# UI.net
KiCad netlist of a schematic drawn in Altium Designer
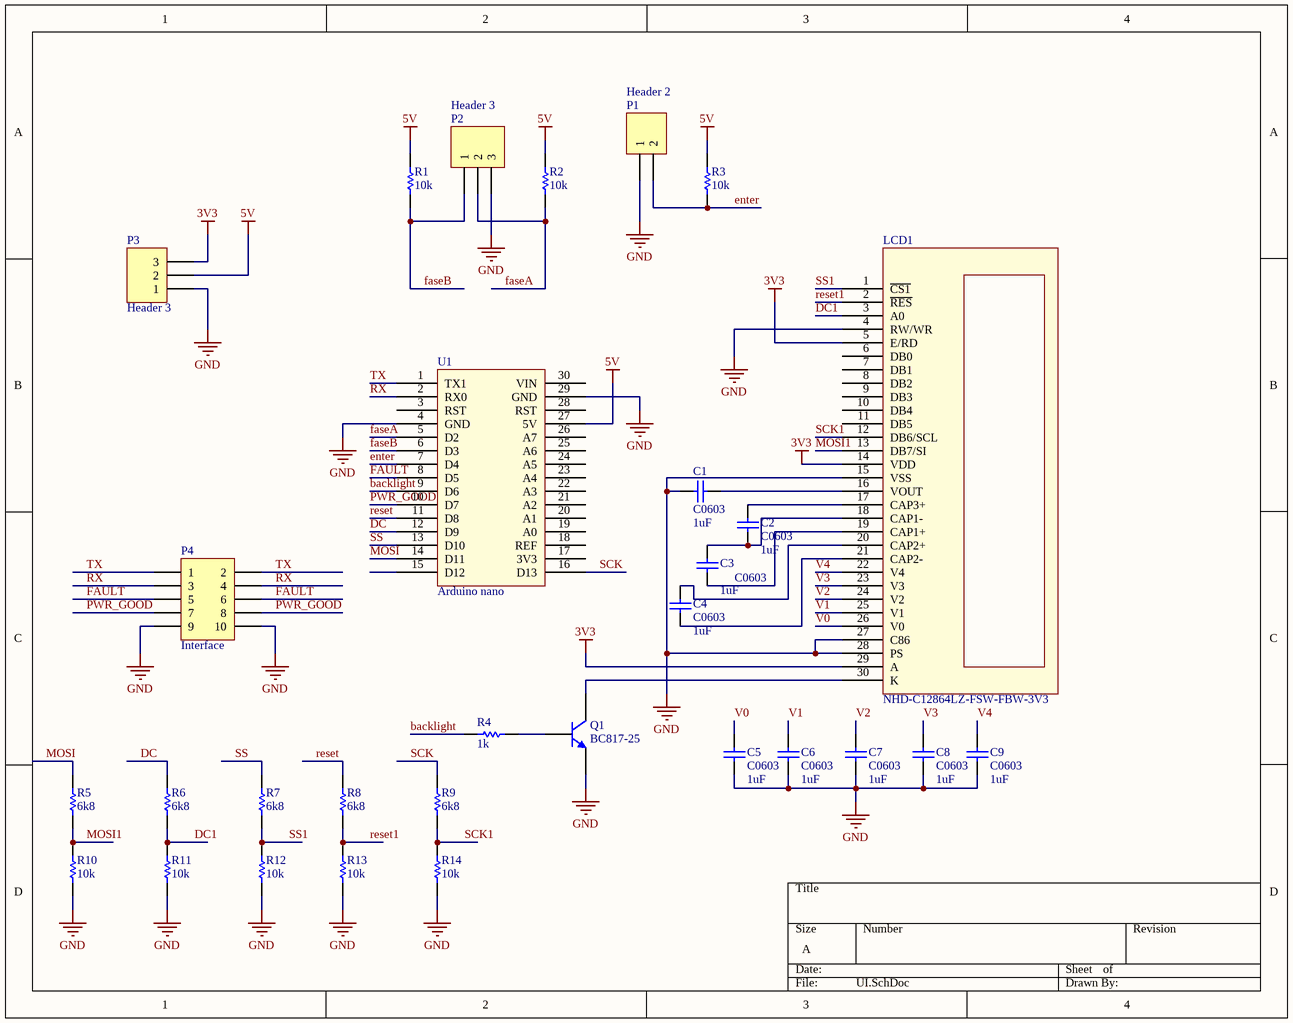
[diagram p0: UI.SchDoc]

(export (version "E")
  (design (tool "Eeschema 10.0.6"))
  (components
    (comp (ref "C1")
      (value "C0603")
      (footprint "0603")
      (description "C1608X7R1C105K X7R")
      (fields (field (name "ALTIUM_VALUE") "1uF") (field (name "PUBLISHER") "Altium Limited"))
      (libsource (lib "KEMET Chip Capacitor") (part "C0603"))
    )
    (comp (ref "C2")
      (value "C0603")
      (footprint "0603")
      (description "C1608X7R1C105K X7R")
      (fields (field (name "ALTIUM_VALUE") "1uF") (field (name "PUBLISHER") "Altium Limited"))
      (libsource (lib "KEMET Chip Capacitor") (part "C0603"))
    )
    (comp (ref "C3")
      (value "C0603")
      (footprint "0603")
      (description "C1608X7R1C105K X7R")
      (fields (field (name "ALTIUM_VALUE") "1uF") (field (name "PUBLISHER") "Altium Limited"))
      (libsource (lib "KEMET Chip Capacitor") (part "C0603"))
    )
    (comp (ref "C4")
      (value "C0603")
      (footprint "0603")
      (description "C1608X7R1C105K X7R")
      (fields (field (name "ALTIUM_VALUE") "1uF") (field (name "PUBLISHER") "Altium Limited"))
      (libsource (lib "KEMET Chip Capacitor") (part "C0603"))
    )
    (comp (ref "C5")
      (value "C0603")
      (footprint "0603")
      (description "C1608X7R1C105K X7R")
      (fields (field (name "ALTIUM_VALUE") "1uF") (field (name "PUBLISHER") "Altium Limited"))
      (libsource (lib "KEMET Chip Capacitor") (part "C0603"))
    )
    (comp (ref "C6")
      (value "C0603")
      (footprint "0603")
      (description "C1608X7R1C105K X7R")
      (fields (field (name "ALTIUM_VALUE") "1uF") (field (name "PUBLISHER") "Altium Limited"))
      (libsource (lib "KEMET Chip Capacitor") (part "C0603"))
    )
    (comp (ref "C7")
      (value "C0603")
      (footprint "0603")
      (description "C1608X7R1C105K X7R")
      (fields (field (name "ALTIUM_VALUE") "1uF") (field (name "PUBLISHER") "Altium Limited"))
      (libsource (lib "KEMET Chip Capacitor") (part "C0603"))
    )
    (comp (ref "C8")
      (value "C0603")
      (footprint "0603")
      (description "C1608X7R1C105K X7R")
      (fields (field (name "ALTIUM_VALUE") "1uF") (field (name "PUBLISHER") "Altium Limited"))
      (libsource (lib "KEMET Chip Capacitor") (part "C0603"))
    )
    (comp (ref "C9")
      (value "C0603")
      (footprint "0603")
      (description "C1608X7R1C105K X7R")
      (fields (field (name "ALTIUM_VALUE") "1uF") (field (name "PUBLISHER") "Altium Limited"))
      (libsource (lib "KEMET Chip Capacitor") (part "C0603"))
    )
    (comp (ref "LCD1")
      (value "NHD-C12864LZ-FSW-FBW-3V3")
      (footprint "NHD-C12864LZ-FSW-FBW-3V3")
      (libsource (lib "NXT - IC") (part "NHD-C12864LZ-FSW-FBW-3V3"))
    )
    (comp (ref "P1")
      (value "Header 2")
      (footprint "HDR1X2")
      (description "Header, 2-Pin")
      (fields (field (name "PUBLISHER") "Altium Limited"))
      (libsource (lib "Miscellaneous Connectors") (part "Header 2"))
    )
    (comp (ref "P2")
      (value "Header 3")
      (footprint "HDR1X3")
      (description "Header, 3-Pin")
      (fields (field (name "PUBLISHER") "Altium Limited"))
      (libsource (lib "Miscellaneous Connectors") (part "Header 3"))
    )
    (comp (ref "P3")
      (value "Header 3")
      (footprint "HDR1X3")
      (description "Header, 3-Pin")
      (fields (field (name "PUBLISHER") "Altium Limited"))
      (libsource (lib "") (part "Header 3_1"))
    )
    (comp (ref "P4")
      (value "Interface")
      (footprint "HDR2X5")
      (description "Header, 5-Pin, Dual row")
      (fields (field (name "PUBLISHER") "Altium Limited"))
      (libsource (lib "Miscellaneous Connectors") (part "Header 5X2"))
    )
    (comp (ref "Q1")
      (value "BC817-25")
      (footprint "SOT-23A_N")
      (description "NPN General Purpose Amplifier")
      (fields (field (name "PUBLISHER") "Altium Limited"))
      (libsource (lib "FSC Discrete BJT") (part "BC817-25"))
    )
    (comp (ref "R1")
      (value "10k")
      (footprint "8RB-1206")
      (fields (field (name "Comment") "SMD") (field (name "PUBLISHER") "Altium Limited"))
      (libsource (lib "Panasonic Resistor") (part "ERJ8BQ"))
    )
    (comp (ref "R2")
      (value "10k")
      (footprint "8RB-1206")
      (fields (field (name "Comment") "SMD") (field (name "PUBLISHER") "Altium Limited"))
      (libsource (lib "Panasonic Resistor") (part "ERJ8BQ"))
    )
    (comp (ref "R3")
      (value "10k")
      (footprint "8RB-1206")
      (fields (field (name "Comment") "SMD") (field (name "PUBLISHER") "Altium Limited"))
      (libsource (lib "Panasonic Resistor") (part "ERJ8BQ"))
    )
    (comp (ref "R4")
      (value "1k")
      (footprint "8RB-1206")
      (fields (field (name "Comment") "SMD") (field (name "PUBLISHER") "Altium Limited"))
      (libsource (lib "Panasonic Resistor") (part "ERJ8BQ"))
    )
    (comp (ref "R5")
      (value "6k8")
      (footprint "8RB-1206")
      (fields (field (name "Comment") "SMD") (field (name "PUBLISHER") "Altium Limited"))
      (libsource (lib "Panasonic Resistor") (part "ERJ8BQ"))
    )
    (comp (ref "R6")
      (value "6k8")
      (footprint "8RB-1206")
      (fields (field (name "Comment") "SMD") (field (name "PUBLISHER") "Altium Limited"))
      (libsource (lib "Panasonic Resistor") (part "ERJ8BQ"))
    )
    (comp (ref "R7")
      (value "6k8")
      (footprint "8RB-1206")
      (fields (field (name "Comment") "SMD") (field (name "PUBLISHER") "Altium Limited"))
      (libsource (lib "Panasonic Resistor") (part "ERJ8BQ"))
    )
    (comp (ref "R8")
      (value "6k8")
      (footprint "8RB-1206")
      (fields (field (name "Comment") "SMD") (field (name "PUBLISHER") "Altium Limited"))
      (libsource (lib "Panasonic Resistor") (part "ERJ8BQ"))
    )
    (comp (ref "R9")
      (value "6k8")
      (footprint "8RB-1206")
      (fields (field (name "Comment") "SMD") (field (name "PUBLISHER") "Altium Limited"))
      (libsource (lib "Panasonic Resistor") (part "ERJ8BQ"))
    )
    (comp (ref "R10")
      (value "10k")
      (footprint "8RB-1206")
      (fields (field (name "Comment") "SMD") (field (name "PUBLISHER") "Altium Limited"))
      (libsource (lib "Panasonic Resistor") (part "ERJ8BQ"))
    )
    (comp (ref "R11")
      (value "10k")
      (footprint "8RB-1206")
      (fields (field (name "Comment") "SMD") (field (name "PUBLISHER") "Altium Limited"))
      (libsource (lib "Panasonic Resistor") (part "ERJ8BQ"))
    )
    (comp (ref "R12")
      (value "10k")
      (footprint "8RB-1206")
      (fields (field (name "Comment") "SMD") (field (name "PUBLISHER") "Altium Limited"))
      (libsource (lib "Panasonic Resistor") (part "ERJ8BQ"))
    )
    (comp (ref "R13")
      (value "10k")
      (footprint "8RB-1206")
      (fields (field (name "Comment") "SMD") (field (name "PUBLISHER") "Altium Limited"))
      (libsource (lib "Panasonic Resistor") (part "ERJ8BQ"))
    )
    (comp (ref "R14")
      (value "10k")
      (footprint "8RB-1206")
      (fields (field (name "Comment") "SMD") (field (name "PUBLISHER") "Altium Limited"))
      (libsource (lib "Panasonic Resistor") (part "ERJ8BQ"))
    )
    (comp (ref "U1")
      (value "Arduino nano")
      (footprint "ARDUINO NANO")
      (libsource (lib "NXT") (part "arduino nano"))
    )
  )
  (nets
    (net (code "1") (name "/DC") (class "Default")
      (node (ref "R6") (pin "2") (pinfunction "2_2") (pintype "passive"))
      (node (ref "U1") (pin "12") (pinfunction "D9_12") (pintype "passive"))
    )
    (net (code "2") (name "/DC1") (class "Default")
      (node (ref "LCD1") (pin "3") (pinfunction "A0_3") (pintype "passive"))
      (node (ref "R11") (pin "2") (pinfunction "2_2") (pintype "passive"))
      (node (ref "R6") (pin "1") (pinfunction "1_1") (pintype "passive"))
    )
    (net (code "3") (name "/FAULT") (class "Default")
      (node (ref "P4") (pin "5") (pinfunction "5_5") (pintype "passive"))
      (node (ref "P4") (pin "6") (pinfunction "6_6") (pintype "passive"))
      (node (ref "U1") (pin "8") (pinfunction "D5_8") (pintype "passive"))
    )
    (net (code "4") (name "/MOSI") (class "Default")
      (node (ref "R5") (pin "2") (pinfunction "2_2") (pintype "passive"))
      (node (ref "U1") (pin "14") (pinfunction "D11_14") (pintype "passive"))
    )
    (net (code "5") (name "/MOSI1") (class "Default")
      (node (ref "LCD1") (pin "13") (pinfunction "DB7/SI_13") (pintype "passive"))
      (node (ref "R10") (pin "2") (pinfunction "2_2") (pintype "passive"))
      (node (ref "R5") (pin "1") (pinfunction "1_1") (pintype "passive"))
    )
    (net (code "6") (name "/PWR_GOOD") (class "Default")
      (node (ref "P4") (pin "7") (pinfunction "7_7") (pintype "passive"))
      (node (ref "P4") (pin "8") (pinfunction "8_8") (pintype "passive"))
      (node (ref "U1") (pin "10") (pinfunction "D7_10") (pintype "passive"))
    )
    (net (code "7") (name "/RX") (class "Default")
      (node (ref "P4") (pin "3") (pinfunction "3_3") (pintype "passive"))
      (node (ref "P4") (pin "4") (pinfunction "4_4") (pintype "passive"))
      (node (ref "U1") (pin "2") (pinfunction "RX0_2") (pintype "passive"))
    )
    (net (code "8") (name "/SCK") (class "Default")
      (node (ref "R9") (pin "2") (pinfunction "2_2") (pintype "passive"))
      (node (ref "U1") (pin "16") (pinfunction "D13_16") (pintype "passive"))
    )
    (net (code "9") (name "/SCK1") (class "Default")
      (node (ref "LCD1") (pin "12") (pinfunction "DB6/SCL_12") (pintype "passive"))
      (node (ref "R14") (pin "2") (pinfunction "2_2") (pintype "passive"))
      (node (ref "R9") (pin "1") (pinfunction "1_1") (pintype "passive"))
    )
    (net (code "10") (name "/SS") (class "Default")
      (node (ref "R7") (pin "2") (pinfunction "2_2") (pintype "passive"))
      (node (ref "U1") (pin "13") (pinfunction "D10_13") (pintype "passive"))
    )
    (net (code "11") (name "/SS1") (class "Default")
      (node (ref "LCD1") (pin "1") (pinfunction "~{CS1}_1") (pintype "passive"))
      (node (ref "R12") (pin "2") (pinfunction "2_2") (pintype "passive"))
      (node (ref "R7") (pin "1") (pinfunction "1_1") (pintype "passive"))
    )
    (net (code "12") (name "/TX") (class "Default")
      (node (ref "P4") (pin "1") (pinfunction "1_1") (pintype "passive"))
      (node (ref "P4") (pin "2") (pinfunction "2_2") (pintype "passive"))
      (node (ref "U1") (pin "1") (pinfunction "TX1_1") (pintype "passive"))
    )
    (net (code "13") (name "/V0") (class "Default")
      (node (ref "C5") (pin "2") (pinfunction "2_2") (pintype "passive"))
      (node (ref "LCD1") (pin "26") (pinfunction "V0_26") (pintype "passive"))
    )
    (net (code "14") (name "/V1") (class "Default")
      (node (ref "C6") (pin "2") (pinfunction "2_2") (pintype "passive"))
      (node (ref "LCD1") (pin "25") (pinfunction "V1_25") (pintype "passive"))
    )
    (net (code "15") (name "/V2") (class "Default")
      (node (ref "C7") (pin "2") (pinfunction "2_2") (pintype "passive"))
      (node (ref "LCD1") (pin "24") (pinfunction "V2_24") (pintype "passive"))
    )
    (net (code "16") (name "/V3") (class "Default")
      (node (ref "C8") (pin "2") (pinfunction "2_2") (pintype "passive"))
      (node (ref "LCD1") (pin "23") (pinfunction "V3_23") (pintype "passive"))
    )
    (net (code "17") (name "/V4") (class "Default")
      (node (ref "C9") (pin "2") (pinfunction "2_2") (pintype "passive"))
      (node (ref "LCD1") (pin "22") (pinfunction "V4_22") (pintype "passive"))
    )
    (net (code "18") (name "/backlight") (class "Default")
      (node (ref "R4") (pin "2") (pinfunction "2_2") (pintype "passive"))
      (node (ref "U1") (pin "9") (pinfunction "D6_9") (pintype "passive"))
    )
    (net (code "19") (name "/enter") (class "Default")
      (node (ref "P1") (pin "2") (pinfunction "2_2") (pintype "passive"))
      (node (ref "R3") (pin "1") (pinfunction "1_1") (pintype "passive"))
      (node (ref "U1") (pin "7") (pinfunction "D4_7") (pintype "passive"))
    )
    (net (code "20") (name "/faseA") (class "Default")
      (node (ref "P2") (pin "2") (pinfunction "2_2") (pintype "passive"))
      (node (ref "R2") (pin "1") (pinfunction "1_1") (pintype "passive"))
      (node (ref "U1") (pin "5") (pinfunction "D2_5") (pintype "passive"))
    )
    (net (code "21") (name "/faseB") (class "Default")
      (node (ref "P2") (pin "1") (pinfunction "1_1") (pintype "passive"))
      (node (ref "R1") (pin "1") (pinfunction "1_1") (pintype "passive"))
      (node (ref "U1") (pin "6") (pinfunction "D3_6") (pintype "passive"))
    )
    (net (code "22") (name "/reset") (class "Default")
      (node (ref "R8") (pin "2") (pinfunction "2_2") (pintype "passive"))
      (node (ref "U1") (pin "11") (pinfunction "D8_11") (pintype "passive"))
    )
    (net (code "23") (name "/reset1") (class "Default")
      (node (ref "LCD1") (pin "2") (pinfunction "~{RES}_2") (pintype "passive"))
      (node (ref "R13") (pin "2") (pinfunction "2_2") (pintype "passive"))
      (node (ref "R8") (pin "1") (pinfunction "1_1") (pintype "passive"))
    )
    (net (code "24") (name "3V3") (class "Default")
      (node (ref "LCD1") (pin "14") (pinfunction "VDD_14") (pintype "passive"))
      (node (ref "LCD1") (pin "29") (pinfunction "A_29") (pintype "passive"))
      (node (ref "LCD1") (pin "5") (pinfunction "E/RD_5") (pintype "passive"))
      (node (ref "P3") (pin "3") (pinfunction "3_3") (pintype "passive"))
    )
    (net (code "25") (name "5V") (class "Default")
      (node (ref "P3") (pin "2") (pinfunction "2_2") (pintype "passive"))
      (node (ref "R1") (pin "2") (pinfunction "2_2") (pintype "passive"))
      (node (ref "R2") (pin "2") (pinfunction "2_2") (pintype "passive"))
      (node (ref "R3") (pin "2") (pinfunction "2_2") (pintype "passive"))
      (node (ref "U1") (pin "27") (pinfunction "5V_27") (pintype "passive"))
    )
    (net (code "26") (name "GND") (class "Default")
      (node (ref "C1") (pin "2") (pinfunction "2_2") (pintype "passive"))
      (node (ref "C5") (pin "1") (pinfunction "1_1") (pintype "passive"))
      (node (ref "C6") (pin "1") (pinfunction "1_1") (pintype "passive"))
      (node (ref "C7") (pin "1") (pinfunction "1_1") (pintype "passive"))
      (node (ref "C8") (pin "1") (pinfunction "1_1") (pintype "passive"))
      (node (ref "C9") (pin "1") (pinfunction "1_1") (pintype "passive"))
      (node (ref "LCD1") (pin "15") (pinfunction "VSS_15") (pintype "passive"))
      (node (ref "LCD1") (pin "27") (pinfunction "C86_27") (pintype "passive"))
      (node (ref "LCD1") (pin "28") (pinfunction "PS_28") (pintype "passive"))
      (node (ref "LCD1") (pin "4") (pinfunction "RW/WR_4") (pintype "passive"))
      (node (ref "P1") (pin "1") (pinfunction "1_1") (pintype "passive"))
      (node (ref "P2") (pin "3") (pinfunction "3_3") (pintype "passive"))
      (node (ref "P3") (pin "1") (pinfunction "1_1") (pintype "passive"))
      (node (ref "P4") (pin "10") (pinfunction "10_10") (pintype "passive"))
      (node (ref "P4") (pin "9") (pinfunction "9_9") (pintype "passive"))
      (node (ref "Q1") (pin "2") (pinfunction "E_2") (pintype "passive"))
      (node (ref "R10") (pin "1") (pinfunction "1_1") (pintype "passive"))
      (node (ref "R11") (pin "1") (pinfunction "1_1") (pintype "passive"))
      (node (ref "R12") (pin "1") (pinfunction "1_1") (pintype "passive"))
      (node (ref "R13") (pin "1") (pinfunction "1_1") (pintype "passive"))
      (node (ref "R14") (pin "1") (pinfunction "1_1") (pintype "passive"))
      (node (ref "U1") (pin "29") (pinfunction "GND_29") (pintype "passive"))
      (node (ref "U1") (pin "4") (pinfunction "GND_4") (pintype "passive"))
    )
    (net (code "27") (name "Net-(LCD1-CAP1+)") (class "Default")
      (node (ref "C3") (pin "1") (pinfunction "1_1") (pintype "passive"))
      (node (ref "LCD1") (pin "19") (pinfunction "CAP1+_19") (pintype "passive"))
    )
    (net (code "28") (name "Net-(LCD1-CAP1-)") (class "Default")
      (node (ref "C2") (pin "1") (pinfunction "1_1") (pintype "passive"))
      (node (ref "C3") (pin "2") (pinfunction "2_2") (pintype "passive"))
      (node (ref "LCD1") (pin "18") (pinfunction "CAP1-_18") (pintype "passive"))
    )
    (net (code "29") (name "Net-(LCD1-CAP2+)") (class "Default")
      (node (ref "C4") (pin "2") (pinfunction "2_2") (pintype "passive"))
      (node (ref "LCD1") (pin "20") (pinfunction "CAP2+_20") (pintype "passive"))
    )
    (net (code "30") (name "Net-(LCD1-CAP2-)") (class "Default")
      (node (ref "C4") (pin "1") (pinfunction "1_1") (pintype "passive"))
      (node (ref "LCD1") (pin "21") (pinfunction "CAP2-_21") (pintype "passive"))
    )
    (net (code "31") (name "Net-(LCD1-CAP3+)") (class "Default")
      (node (ref "C2") (pin "2") (pinfunction "2_2") (pintype "passive"))
      (node (ref "LCD1") (pin "17") (pinfunction "CAP3+_17") (pintype "passive"))
    )
    (net (code "32") (name "Net-(LCD1-K)") (class "Default")
      (node (ref "LCD1") (pin "30") (pinfunction "K_30") (pintype "passive"))
      (node (ref "Q1") (pin "3") (pinfunction "C_3") (pintype "passive"))
    )
    (net (code "33") (name "Net-(LCD1-VOUT)") (class "Default")
      (node (ref "C1") (pin "1") (pinfunction "1_1") (pintype "passive"))
      (node (ref "LCD1") (pin "16") (pinfunction "VOUT_16") (pintype "passive"))
    )
    (net (code "34") (name "Net-(Q1-B)") (class "Default")
      (node (ref "Q1") (pin "1") (pinfunction "B_1") (pintype "passive"))
      (node (ref "R4") (pin "1") (pinfunction "1_1") (pintype "passive"))
    )
    (net (code "35") (name "unconnected-(LCD1-DB0-Pad6)") (class "Default")
      (node (ref "LCD1") (pin "6") (pinfunction "DB0_6") (pintype "passive"))
    )
    (net (code "36") (name "unconnected-(LCD1-DB1-Pad7)") (class "Default")
      (node (ref "LCD1") (pin "7") (pinfunction "DB1_7") (pintype "passive"))
    )
    (net (code "37") (name "unconnected-(LCD1-DB2-Pad8)") (class "Default")
      (node (ref "LCD1") (pin "8") (pinfunction "DB2_8") (pintype "passive"))
    )
    (net (code "38") (name "unconnected-(LCD1-DB3-Pad9)") (class "Default")
      (node (ref "LCD1") (pin "9") (pinfunction "DB3_9") (pintype "passive"))
    )
    (net (code "39") (name "unconnected-(LCD1-DB4-Pad10)") (class "Default")
      (node (ref "LCD1") (pin "10") (pinfunction "DB4_10") (pintype "passive"))
    )
    (net (code "40") (name "unconnected-(LCD1-DB5-Pad11)") (class "Default")
      (node (ref "LCD1") (pin "11") (pinfunction "DB5_11") (pintype "passive"))
    )
    (net (code "41") (name "unconnected-(U1-3V3-Pad17)") (class "Default")
      (node (ref "U1") (pin "17") (pinfunction "3V3_17") (pintype "passive"))
    )
    (net (code "42") (name "unconnected-(U1-A0-Pad19)") (class "Default")
      (node (ref "U1") (pin "19") (pinfunction "A0_19") (pintype "passive"))
    )
    (net (code "43") (name "unconnected-(U1-A1-Pad20)") (class "Default")
      (node (ref "U1") (pin "20") (pinfunction "A1_20") (pintype "passive"))
    )
    (net (code "44") (name "unconnected-(U1-A2-Pad21)") (class "Default")
      (node (ref "U1") (pin "21") (pinfunction "A2_21") (pintype "passive"))
    )
    (net (code "45") (name "unconnected-(U1-A3-Pad22)") (class "Default")
      (node (ref "U1") (pin "22") (pinfunction "A3_22") (pintype "passive"))
    )
    (net (code "46") (name "unconnected-(U1-A4-Pad23)") (class "Default")
      (node (ref "U1") (pin "23") (pinfunction "A4_23") (pintype "passive"))
    )
    (net (code "47") (name "unconnected-(U1-A5-Pad24)") (class "Default")
      (node (ref "U1") (pin "24") (pinfunction "A5_24") (pintype "passive"))
    )
    (net (code "48") (name "unconnected-(U1-A6-Pad25)") (class "Default")
      (node (ref "U1") (pin "25") (pinfunction "A6_25") (pintype "passive"))
    )
    (net (code "49") (name "unconnected-(U1-A7-Pad26)") (class "Default")
      (node (ref "U1") (pin "26") (pinfunction "A7_26") (pintype "passive"))
    )
    (net (code "50") (name "unconnected-(U1-D12-Pad15)") (class "Default")
      (node (ref "U1") (pin "15") (pinfunction "D12_15") (pintype "passive"))
    )
    (net (code "51") (name "unconnected-(U1-REF-Pad18)") (class "Default")
      (node (ref "U1") (pin "18") (pinfunction "REF_18") (pintype "passive"))
    )
    (net (code "52") (name "unconnected-(U1-RST-Pad3)") (class "Default")
      (node (ref "U1") (pin "3") (pinfunction "RST_3") (pintype "passive"))
    )
    (net (code "53") (name "unconnected-(U1-RST-Pad28)") (class "Default")
      (node (ref "U1") (pin "28") (pinfunction "RST_28") (pintype "passive"))
    )
    (net (code "54") (name "unconnected-(U1-VIN-Pad30)") (class "Default")
      (node (ref "U1") (pin "30") (pinfunction "VIN_30") (pintype "passive"))
    )
  )
)
